# SWITCHING.net
KiCad netlist of a schematic drawn in Altium Designer
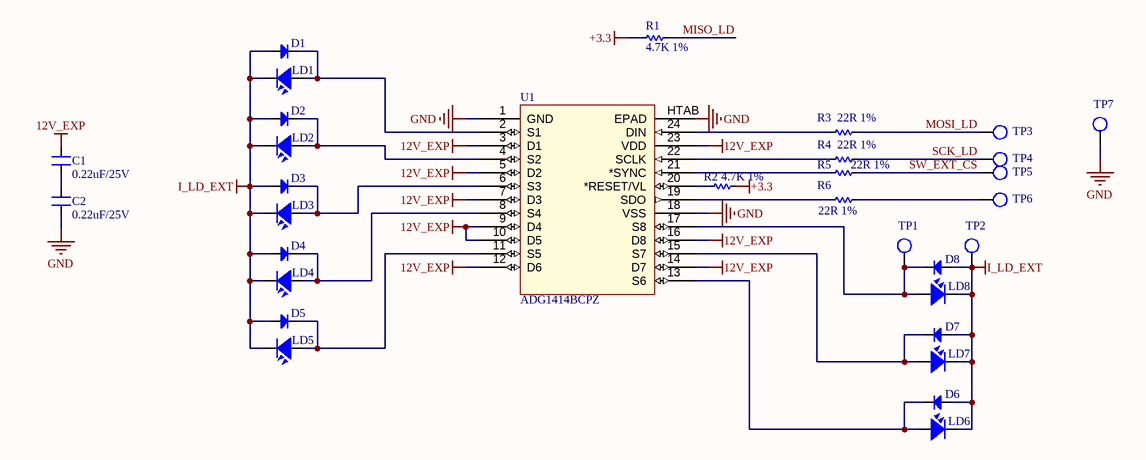
[diagram p0: SWITCHING.SchDoc]

(export (version "E")
  (design (tool "Eeschema 10.0.6"))
  (components
    (comp (ref "C1")
      (value "0.22uF/25V")
      (footprint "CN-SMD-0603")
      (description "CAP CER 0.22UF 25V X7R 0603")
      (libsource (lib "Library") (part "CN"))
    )
    (comp (ref "C2")
      (value "0.22uF/25V")
      (footprint "CN-SMD-0603")
      (description "CAP CER 0.22UF 25V X7R 0603")
      (libsource (lib "Library") (part "CN"))
    )
    (comp (ref "D1")
      (value "1N4148W-TP")
      (footprint "SOD123")
      (description "DIODE STANDARD 100V 150MA SOD123")
      (fields (field (name "PUBLISHER") "Altium Limited"))
      (libsource (lib "Library") (part "Diode SMD"))
    )
    (comp (ref "D2")
      (value "1N4148W-TP")
      (footprint "SOD123")
      (description "DIODE STANDARD 100V 150MA SOD123")
      (fields (field (name "PUBLISHER") "Altium Limited"))
      (libsource (lib "Library") (part "Diode SMD"))
    )
    (comp (ref "D3")
      (value "1N4148W-TP")
      (footprint "SOD123")
      (description "DIODE STANDARD 100V 150MA SOD123")
      (fields (field (name "PUBLISHER") "Altium Limited"))
      (libsource (lib "Library") (part "Diode SMD"))
    )
    (comp (ref "D4")
      (value "1N4148W-TP")
      (footprint "SOD123")
      (description "DIODE STANDARD 100V 150MA SOD123")
      (fields (field (name "PUBLISHER") "Altium Limited"))
      (libsource (lib "Library") (part "Diode SMD"))
    )
    (comp (ref "D5")
      (value "1N4148W-TP")
      (footprint "SOD123")
      (description "DIODE STANDARD 100V 150MA SOD123")
      (fields (field (name "PUBLISHER") "Altium Limited"))
      (libsource (lib "Library") (part "Diode SMD"))
    )
    (comp (ref "D6")
      (value "1N4148W-TP")
      (footprint "SOD123")
      (description "DIODE STANDARD 100V 150MA SOD123")
      (fields (field (name "PUBLISHER") "Altium Limited"))
      (libsource (lib "Library") (part "Diode SMD"))
    )
    (comp (ref "D7")
      (value "1N4148W-TP")
      (footprint "SOD123")
      (description "DIODE STANDARD 100V 150MA SOD123")
      (fields (field (name "PUBLISHER") "Altium Limited"))
      (libsource (lib "Library") (part "Diode SMD"))
    )
    (comp (ref "D8")
      (value "1N4148W-TP")
      (footprint "SOD123")
      (description "DIODE STANDARD 100V 150MA SOD123")
      (fields (field (name "PUBLISHER") "Altium Limited"))
      (libsource (lib "Library") (part "Diode SMD"))
    )
    (comp (ref "LD1")
      (value "LaserDiode")
      (footprint "LASER_SOCKET")
      (libsource (lib "Library") (part "LASER"))
    )
    (comp (ref "LD2")
      (value "LaserDiode")
      (footprint "LASER_SOCKET")
      (libsource (lib "Library") (part "LASER"))
    )
    (comp (ref "LD3")
      (value "LaserDiode")
      (footprint "LASER_SOCKET")
      (libsource (lib "Library") (part "LASER"))
    )
    (comp (ref "LD4")
      (value "LaserDiode")
      (footprint "LASER_SOCKET")
      (libsource (lib "Library") (part "LASER"))
    )
    (comp (ref "LD5")
      (value "LaserDiode")
      (footprint "LASER_SOCKET")
      (libsource (lib "Library") (part "LASER"))
    )
    (comp (ref "LD6")
      (value "LaserDiode")
      (footprint "LASER_SOCKET")
      (libsource (lib "Library") (part "LASER"))
    )
    (comp (ref "LD7")
      (value "LaserDiode")
      (footprint "LASER_SOCKET")
      (libsource (lib "Library") (part "LASER"))
    )
    (comp (ref "LD8")
      (value "LaserDiode")
      (footprint "LASER_SOCKET")
      (libsource (lib "Library") (part "LASER"))
    )
    (comp (ref "R1")
      (value "4.7K 1%")
      (footprint "RES-SMD-0603")
      (description "RES SMD 4.7K OHM 1% 1/10W 0603")
      (fields
        (field (name "MANUFACTURER") "Generic Components")
        (field (name "PUBLISHER") "Altium Hobart Technology Centre")
      )
      (libsource (lib "Library") (part "Res-SMD"))
    )
    (comp (ref "R2")
      (value "4.7K 1%")
      (footprint "RES-SMD-0603")
      (description "RES SMD 4.7K OHM 1% 1/10W 0603")
      (fields
        (field (name "MANUFACTURER") "Generic Components")
        (field (name "PUBLISHER") "Altium Hobart Technology Centre")
      )
      (libsource (lib "Library") (part "Res-SMD"))
    )
    (comp (ref "R3")
      (value "22R 1%")
      (footprint "RES-SMD-0603")
      (description "Resistor")
      (fields
        (field (name "MANUFACTURER") "Generic Components")
        (field (name "PUBLISHER") "Altium Hobart Technology Centre")
      )
      (libsource (lib "Library") (part "Res-SMD"))
    )
    (comp (ref "R4")
      (value "22R 1%")
      (footprint "RES-SMD-0603")
      (description "Resistor")
      (fields
        (field (name "MANUFACTURER") "Generic Components")
        (field (name "PUBLISHER") "Altium Hobart Technology Centre")
      )
      (libsource (lib "Library") (part "Res-SMD"))
    )
    (comp (ref "R5")
      (value "22R 1%")
      (footprint "RES-SMD-0603")
      (description "Resistor")
      (fields
        (field (name "MANUFACTURER") "Generic Components")
        (field (name "PUBLISHER") "Altium Hobart Technology Centre")
      )
      (libsource (lib "Library") (part "Res-SMD"))
    )
    (comp (ref "R6")
      (value "22R 1%")
      (footprint "RES-SMD-0603")
      (description "Resistor")
      (fields
        (field (name "MANUFACTURER") "Generic Components")
        (field (name "PUBLISHER") "Altium Hobart Technology Centre")
      )
      (libsource (lib "Library") (part "Res-SMD"))
    )
    (comp (ref "TP1")
      (value "Test-Point")
      (footprint "TESTPOINT")
      (libsource (lib "Library") (part "Test-Point"))
    )
    (comp (ref "TP2")
      (value "Test-Point")
      (footprint "TESTPOINT")
      (libsource (lib "Library") (part "Test-Point"))
    )
    (comp (ref "TP3")
      (value "Test-Point")
      (footprint "TESTPOINT")
      (libsource (lib "Library") (part "Test-Point"))
    )
    (comp (ref "TP4")
      (value "Test-Point")
      (footprint "TESTPOINT")
      (libsource (lib "Library") (part "Test-Point"))
    )
    (comp (ref "TP5")
      (value "Test-Point")
      (footprint "TESTPOINT")
      (libsource (lib "Library") (part "Test-Point"))
    )
    (comp (ref "TP6")
      (value "Test-Point")
      (footprint "TESTPOINT")
      (libsource (lib "Library") (part "Test-Point"))
    )
    (comp (ref "TP7")
      (value "Test-Point")
      (footprint "TESTPOINT")
      (libsource (lib "Library") (part "Test-Point"))
    )
    (comp (ref "U1")
      (value "ADG1414BCPZ")
      (footprint "ADG1414BCPZ")
      (description "IC SW SPST-NOX8 11.5OHM 24LFCSP")
      (libsource (lib "Library") (part "ADG1414BCPZ"))
    )
  )
  (nets
    (net (code "1") (name "+3.3") (class "Default")
      (node (ref "R1") (pin "1") (pinfunction "1_1") (pintype "passive"))
      (node (ref "R2") (pin "1") (pinfunction "1_1") (pintype "passive"))
    )
    (net (code "2") (name "/MISO_LD") (class "Default")
      (node (ref "R1") (pin "2") (pinfunction "2_2") (pintype "passive"))
    )
    (net (code "3") (name "/MOSI_LD") (class "Default")
      (node (ref "R3") (pin "1") (pinfunction "1_1") (pintype "passive"))
      (node (ref "TP3") (pin "1") (pinfunction "1_1") (pintype "passive"))
    )
    (net (code "4") (name "/SCK_LD") (class "Default")
      (node (ref "R4") (pin "1") (pinfunction "1_1") (pintype "passive"))
      (node (ref "TP4") (pin "1") (pinfunction "1_1") (pintype "passive"))
    )
    (net (code "5") (name "/SW_EXT_CS") (class "Default")
      (node (ref "R5") (pin "1") (pinfunction "1_1") (pintype "passive"))
      (node (ref "TP5") (pin "1") (pinfunction "1_1") (pintype "passive"))
    )
    (net (code "6") (name "12V_EXP") (class "Default")
      (node (ref "C1") (pin "2") (pinfunction "2_2") (pintype "passive"))
      (node (ref "U1") (pin "10") (pinfunction "D5_10") (pintype "bidirectional"))
      (node (ref "U1") (pin "12") (pinfunction "D6_12") (pintype "bidirectional"))
      (node (ref "U1") (pin "14") (pinfunction "D7_14") (pintype "bidirectional"))
      (node (ref "U1") (pin "16") (pinfunction "D8_16") (pintype "bidirectional"))
      (node (ref "U1") (pin "23") (pinfunction "VDD_23") (pintype "power_in"))
      (node (ref "U1") (pin "3") (pinfunction "D1_3") (pintype "bidirectional"))
      (node (ref "U1") (pin "5") (pinfunction "D2_5") (pintype "bidirectional"))
      (node (ref "U1") (pin "7") (pinfunction "D3_7") (pintype "bidirectional"))
      (node (ref "U1") (pin "9") (pinfunction "D4_9") (pintype "bidirectional"))
    )
    (net (code "7") (name "GND") (class "Default")
      (node (ref "C2") (pin "1") (pinfunction "1_1") (pintype "passive"))
      (node (ref "TP7") (pin "1") (pinfunction "1_1") (pintype "passive"))
      (node (ref "U1") (pin "1") (pinfunction "GND_1") (pintype "power_in"))
      (node (ref "U1") (pin "18") (pinfunction "VSS_18") (pintype "power_in"))
      (node (ref "U1") (pin "HTAB") (pinfunction "EPAD_HTAB") (pintype "passive"))
    )
    (net (code "8") (name "I_LD_EXT") (class "Default")
      (node (ref "D1") (pin "1") (pinfunction "A_1") (pintype "passive"))
      (node (ref "D2") (pin "1") (pinfunction "A_1") (pintype "passive"))
      (node (ref "D3") (pin "1") (pinfunction "A_1") (pintype "passive"))
      (node (ref "D4") (pin "1") (pinfunction "A_1") (pintype "passive"))
      (node (ref "D5") (pin "1") (pinfunction "A_1") (pintype "passive"))
      (node (ref "D6") (pin "1") (pinfunction "A_1") (pintype "passive"))
      (node (ref "D7") (pin "1") (pinfunction "A_1") (pintype "passive"))
      (node (ref "D8") (pin "1") (pinfunction "A_1") (pintype "passive"))
      (node (ref "LD1") (pin "3") (pinfunction "3_3") (pintype "passive"))
      (node (ref "LD2") (pin "3") (pinfunction "3_3") (pintype "passive"))
      (node (ref "LD3") (pin "3") (pinfunction "3_3") (pintype "passive"))
      (node (ref "LD4") (pin "3") (pinfunction "3_3") (pintype "passive"))
      (node (ref "LD5") (pin "3") (pinfunction "3_3") (pintype "passive"))
      (node (ref "LD6") (pin "3") (pinfunction "3_3") (pintype "passive"))
      (node (ref "LD7") (pin "3") (pinfunction "3_3") (pintype "passive"))
      (node (ref "LD8") (pin "3") (pinfunction "3_3") (pintype "passive"))
      (node (ref "TP2") (pin "1") (pinfunction "1_1") (pintype "passive"))
    )
    (net (code "9") (name "Net-(C1-Pad1)") (class "Default")
      (node (ref "C1") (pin "1") (pinfunction "1_1") (pintype "passive"))
      (node (ref "C2") (pin "2") (pinfunction "2_2") (pintype "passive"))
    )
    (net (code "10") (name "Net-(D1-K)") (class "Default")
      (node (ref "D1") (pin "2") (pinfunction "K_2") (pintype "passive"))
      (node (ref "LD1") (pin "1") (pinfunction "1_1") (pintype "passive"))
      (node (ref "U1") (pin "2") (pinfunction "S1_2") (pintype "bidirectional"))
    )
    (net (code "11") (name "Net-(D2-K)") (class "Default")
      (node (ref "D2") (pin "2") (pinfunction "K_2") (pintype "passive"))
      (node (ref "LD2") (pin "1") (pinfunction "1_1") (pintype "passive"))
      (node (ref "U1") (pin "4") (pinfunction "S2_4") (pintype "bidirectional"))
    )
    (net (code "12") (name "Net-(D3-K)") (class "Default")
      (node (ref "D3") (pin "2") (pinfunction "K_2") (pintype "passive"))
      (node (ref "LD3") (pin "1") (pinfunction "1_1") (pintype "passive"))
      (node (ref "U1") (pin "6") (pinfunction "S3_6") (pintype "bidirectional"))
    )
    (net (code "13") (name "Net-(D4-K)") (class "Default")
      (node (ref "D4") (pin "2") (pinfunction "K_2") (pintype "passive"))
      (node (ref "LD4") (pin "1") (pinfunction "1_1") (pintype "passive"))
      (node (ref "U1") (pin "8") (pinfunction "S4_8") (pintype "bidirectional"))
    )
    (net (code "14") (name "Net-(D5-K)") (class "Default")
      (node (ref "D5") (pin "2") (pinfunction "K_2") (pintype "passive"))
      (node (ref "LD5") (pin "1") (pinfunction "1_1") (pintype "passive"))
      (node (ref "U1") (pin "11") (pinfunction "S5_11") (pintype "bidirectional"))
    )
    (net (code "15") (name "Net-(D6-K)") (class "Default")
      (node (ref "D6") (pin "2") (pinfunction "K_2") (pintype "passive"))
      (node (ref "LD6") (pin "1") (pinfunction "1_1") (pintype "passive"))
      (node (ref "U1") (pin "13") (pinfunction "S6_13") (pintype "bidirectional"))
    )
    (net (code "16") (name "Net-(D7-K)") (class "Default")
      (node (ref "D7") (pin "2") (pinfunction "K_2") (pintype "passive"))
      (node (ref "LD7") (pin "1") (pinfunction "1_1") (pintype "passive"))
      (node (ref "U1") (pin "15") (pinfunction "S7_15") (pintype "bidirectional"))
    )
    (net (code "17") (name "Net-(D8-K)") (class "Default")
      (node (ref "D8") (pin "2") (pinfunction "K_2") (pintype "passive"))
      (node (ref "LD8") (pin "1") (pinfunction "1_1") (pintype "passive"))
      (node (ref "TP1") (pin "1") (pinfunction "1_1") (pintype "passive"))
      (node (ref "U1") (pin "17") (pinfunction "S8_17") (pintype "bidirectional"))
    )
    (net (code "18") (name "Net-(R6-Pad1)") (class "Default")
      (node (ref "R6") (pin "1") (pinfunction "1_1") (pintype "passive"))
      (node (ref "TP6") (pin "1") (pinfunction "1_1") (pintype "passive"))
    )
    (net (code "19") (name "Net-(U1-*RESET{slash}VL)") (class "Default")
      (node (ref "R2") (pin "2") (pinfunction "2_2") (pintype "passive"))
      (node (ref "U1") (pin "20") (pinfunction "*RESET/VL_20") (pintype "bidirectional"))
    )
    (net (code "20") (name "Net-(U1-*SYNC)") (class "Default")
      (node (ref "R5") (pin "2") (pinfunction "2_2") (pintype "passive"))
      (node (ref "U1") (pin "21") (pinfunction "*SYNC_21") (pintype "input"))
    )
    (net (code "21") (name "Net-(U1-DIN)") (class "Default")
      (node (ref "R3") (pin "2") (pinfunction "2_2") (pintype "passive"))
      (node (ref "U1") (pin "24") (pinfunction "DIN_24") (pintype "input"))
    )
    (net (code "22") (name "Net-(U1-SCLK)") (class "Default")
      (node (ref "R4") (pin "2") (pinfunction "2_2") (pintype "passive"))
      (node (ref "U1") (pin "22") (pinfunction "SCLK_22") (pintype "input"))
    )
    (net (code "23") (name "Net-(U1-SDO)") (class "Default")
      (node (ref "R6") (pin "2") (pinfunction "2_2") (pintype "passive"))
      (node (ref "U1") (pin "19") (pinfunction "SDO_19") (pintype "output"))
    )
  )
)
